# led_demo-v2.net
KiCad netlist of a schematic drawn in EAGLE
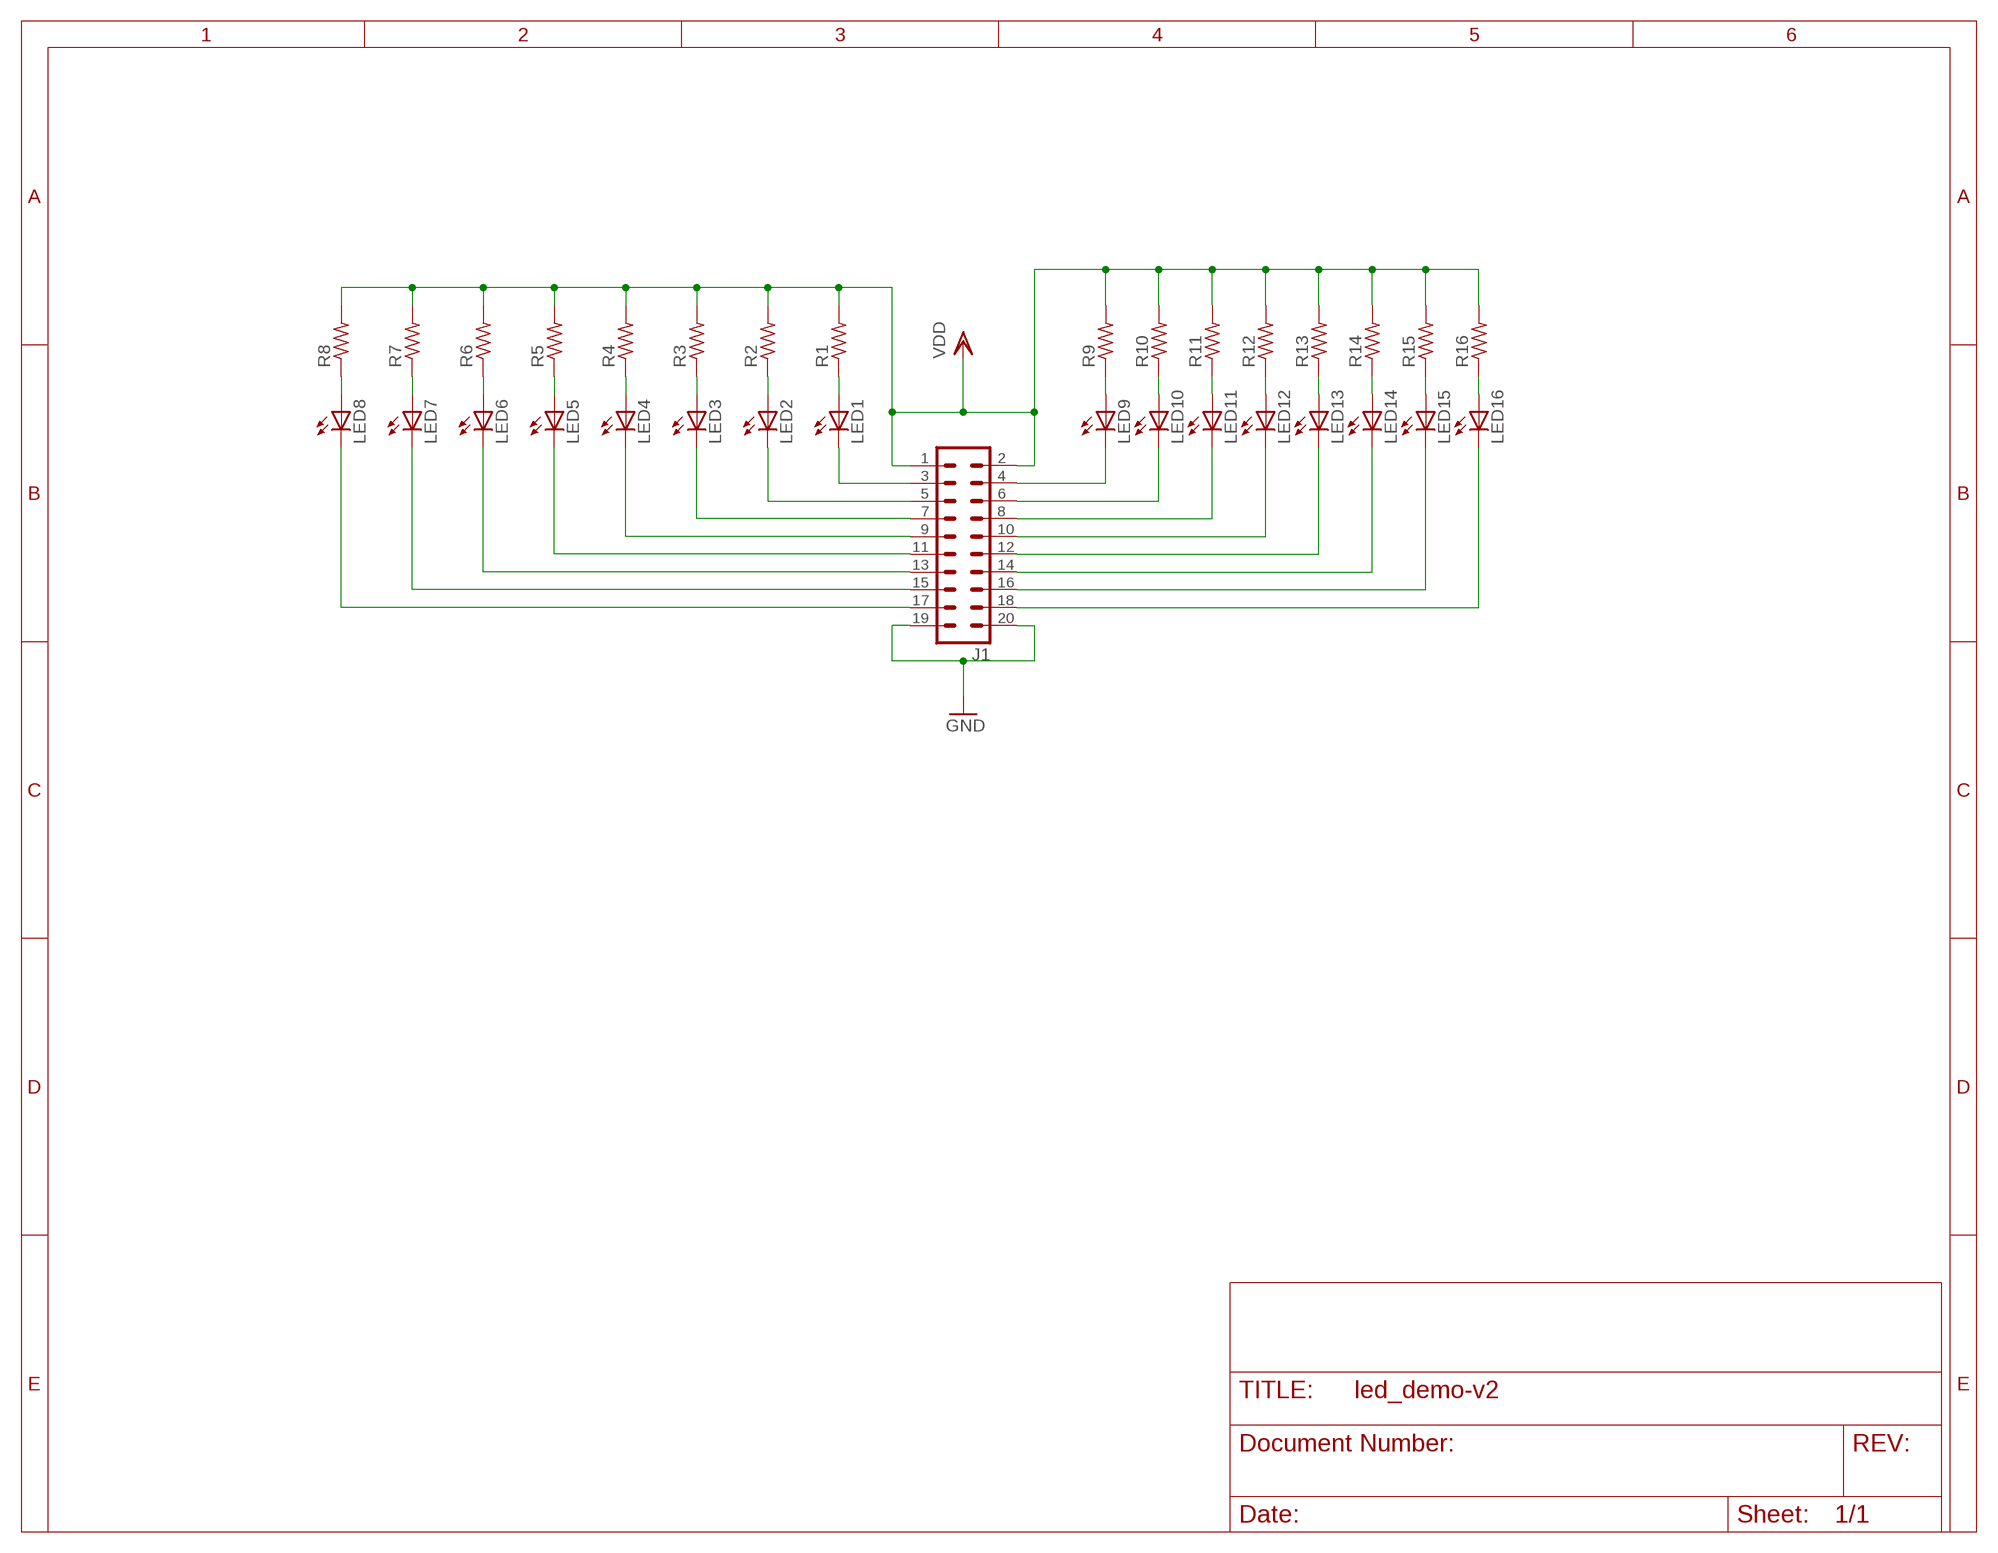
[diagram p0: schematic, sheet 1]

(export (version "E")
  (design (tool "Eeschema 10.0.6"))
  (components
    (comp (ref "J1")
      (value "MA10-2")
      (footprint "eagle-import:MA10-2")
      (libsource (lib "eagle-import") (part "MA10-2"))
    )
    (comp (ref "LED1")
      (value "LED3MM")
      (footprint "eagle-import:LED3MM")
      (libsource (lib "eagle-import") (part "LED3MM"))
    )
    (comp (ref "LED2")
      (value "LED3MM")
      (footprint "eagle-import:LED3MM")
      (libsource (lib "eagle-import") (part "LED3MM"))
    )
    (comp (ref "LED3")
      (value "LED3MM")
      (footprint "eagle-import:LED3MM")
      (libsource (lib "eagle-import") (part "LED3MM"))
    )
    (comp (ref "LED4")
      (value "LED3MM")
      (footprint "eagle-import:LED3MM")
      (libsource (lib "eagle-import") (part "LED3MM"))
    )
    (comp (ref "LED5")
      (value "LED3MM")
      (footprint "eagle-import:LED3MM")
      (libsource (lib "eagle-import") (part "LED3MM"))
    )
    (comp (ref "LED6")
      (value "LED3MM")
      (footprint "eagle-import:LED3MM")
      (libsource (lib "eagle-import") (part "LED3MM"))
    )
    (comp (ref "LED7")
      (value "LED3MM")
      (footprint "eagle-import:LED3MM")
      (libsource (lib "eagle-import") (part "LED3MM"))
    )
    (comp (ref "LED8")
      (value "LED3MM")
      (footprint "eagle-import:LED3MM")
      (libsource (lib "eagle-import") (part "LED3MM"))
    )
    (comp (ref "LED9")
      (value "LED3MM")
      (footprint "eagle-import:LED3MM")
      (libsource (lib "eagle-import") (part "LED3MM"))
    )
    (comp (ref "LED10")
      (value "LED3MM")
      (footprint "eagle-import:LED3MM")
      (libsource (lib "eagle-import") (part "LED3MM"))
    )
    (comp (ref "LED11")
      (value "LED3MM")
      (footprint "eagle-import:LED3MM")
      (libsource (lib "eagle-import") (part "LED3MM"))
    )
    (comp (ref "LED12")
      (value "LED3MM")
      (footprint "eagle-import:LED3MM")
      (libsource (lib "eagle-import") (part "LED3MM"))
    )
    (comp (ref "LED13")
      (value "LED3MM")
      (footprint "eagle-import:LED3MM")
      (libsource (lib "eagle-import") (part "LED3MM"))
    )
    (comp (ref "LED14")
      (value "LED3MM")
      (footprint "eagle-import:LED3MM")
      (libsource (lib "eagle-import") (part "LED3MM"))
    )
    (comp (ref "LED15")
      (value "LED3MM")
      (footprint "eagle-import:LED3MM")
      (libsource (lib "eagle-import") (part "LED3MM"))
    )
    (comp (ref "LED16")
      (value "LED3MM")
      (footprint "eagle-import:LED3MM")
      (libsource (lib "eagle-import") (part "LED3MM"))
    )
    (comp (ref "R1")
      (value "R-US_0204/2V")
      (footprint "eagle-import:0204V")
      (libsource (lib "eagle-import") (part "R-US_0204/2V"))
    )
    (comp (ref "R2")
      (value "R-US_0204/2V")
      (footprint "eagle-import:0204V")
      (libsource (lib "eagle-import") (part "R-US_0204/2V"))
    )
    (comp (ref "R3")
      (value "R-US_0204/2V")
      (footprint "eagle-import:0204V")
      (libsource (lib "eagle-import") (part "R-US_0204/2V"))
    )
    (comp (ref "R4")
      (value "R-US_0204/2V")
      (footprint "eagle-import:0204V")
      (libsource (lib "eagle-import") (part "R-US_0204/2V"))
    )
    (comp (ref "R5")
      (value "R-US_0204/2V")
      (footprint "eagle-import:0204V")
      (libsource (lib "eagle-import") (part "R-US_0204/2V"))
    )
    (comp (ref "R6")
      (value "R-US_0204/2V")
      (footprint "eagle-import:0204V")
      (libsource (lib "eagle-import") (part "R-US_0204/2V"))
    )
    (comp (ref "R7")
      (value "R-US_0204/2V")
      (footprint "eagle-import:0204V")
      (libsource (lib "eagle-import") (part "R-US_0204/2V"))
    )
    (comp (ref "R8")
      (value "R-US_0204/2V")
      (footprint "eagle-import:0204V")
      (libsource (lib "eagle-import") (part "R-US_0204/2V"))
    )
    (comp (ref "R9")
      (value "R-US_0204/2V")
      (footprint "eagle-import:0204V")
      (libsource (lib "eagle-import") (part "R-US_0204/2V"))
    )
    (comp (ref "R10")
      (value "R-US_0204/2V")
      (footprint "eagle-import:0204V")
      (libsource (lib "eagle-import") (part "R-US_0204/2V"))
    )
    (comp (ref "R11")
      (value "R-US_0204/2V")
      (footprint "eagle-import:0204V")
      (libsource (lib "eagle-import") (part "R-US_0204/2V"))
    )
    (comp (ref "R12")
      (value "R-US_0204/2V")
      (footprint "eagle-import:0204V")
      (libsource (lib "eagle-import") (part "R-US_0204/2V"))
    )
    (comp (ref "R13")
      (value "R-US_0204/2V")
      (footprint "eagle-import:0204V")
      (libsource (lib "eagle-import") (part "R-US_0204/2V"))
    )
    (comp (ref "R14")
      (value "R-US_0204/2V")
      (footprint "eagle-import:0204V")
      (libsource (lib "eagle-import") (part "R-US_0204/2V"))
    )
    (comp (ref "R15")
      (value "R-US_0204/2V")
      (footprint "eagle-import:0204V")
      (libsource (lib "eagle-import") (part "R-US_0204/2V"))
    )
    (comp (ref "R16")
      (value "R-US_0204/2V")
      (footprint "eagle-import:0204V")
      (libsource (lib "eagle-import") (part "R-US_0204/2V"))
    )
  )
  (nets
    (net (code "1") (name "GND") (class "Default")
      (node (ref "J1") (pin "19") (pinfunction "19_19") (pintype "passive"))
      (node (ref "J1") (pin "20") (pinfunction "20_20") (pintype "passive"))
    )
    (net (code "2") (name "Net-(LED1-C)") (class "Default")
      (node (ref "J1") (pin "3") (pinfunction "3_3") (pintype "passive"))
      (node (ref "LED1") (pin "K") (pinfunction "C_K") (pintype "passive"))
    )
    (net (code "3") (name "Net-(LED1-PadA)") (class "Default")
      (node (ref "LED1") (pin "A") (pinfunction "A_A") (pintype "passive"))
      (node (ref "R1") (pin "1") (pinfunction "1_1") (pintype "passive"))
    )
    (net (code "4") (name "Net-(LED2-C)") (class "Default")
      (node (ref "J1") (pin "5") (pinfunction "5_5") (pintype "passive"))
      (node (ref "LED2") (pin "K") (pinfunction "C_K") (pintype "passive"))
    )
    (net (code "5") (name "Net-(LED2-PadA)") (class "Default")
      (node (ref "LED2") (pin "A") (pinfunction "A_A") (pintype "passive"))
      (node (ref "R2") (pin "1") (pinfunction "1_1") (pintype "passive"))
    )
    (net (code "6") (name "Net-(LED3-C)") (class "Default")
      (node (ref "J1") (pin "7") (pinfunction "7_7") (pintype "passive"))
      (node (ref "LED3") (pin "K") (pinfunction "C_K") (pintype "passive"))
    )
    (net (code "7") (name "Net-(LED3-PadA)") (class "Default")
      (node (ref "LED3") (pin "A") (pinfunction "A_A") (pintype "passive"))
      (node (ref "R3") (pin "1") (pinfunction "1_1") (pintype "passive"))
    )
    (net (code "8") (name "Net-(LED4-C)") (class "Default")
      (node (ref "J1") (pin "9") (pinfunction "9_9") (pintype "passive"))
      (node (ref "LED4") (pin "K") (pinfunction "C_K") (pintype "passive"))
    )
    (net (code "9") (name "Net-(LED4-PadA)") (class "Default")
      (node (ref "LED4") (pin "A") (pinfunction "A_A") (pintype "passive"))
      (node (ref "R4") (pin "1") (pinfunction "1_1") (pintype "passive"))
    )
    (net (code "10") (name "Net-(LED5-C)") (class "Default")
      (node (ref "J1") (pin "11") (pinfunction "11_11") (pintype "passive"))
      (node (ref "LED5") (pin "K") (pinfunction "C_K") (pintype "passive"))
    )
    (net (code "11") (name "Net-(LED5-PadA)") (class "Default")
      (node (ref "LED5") (pin "A") (pinfunction "A_A") (pintype "passive"))
      (node (ref "R5") (pin "1") (pinfunction "1_1") (pintype "passive"))
    )
    (net (code "12") (name "Net-(LED6-C)") (class "Default")
      (node (ref "J1") (pin "13") (pinfunction "13_13") (pintype "passive"))
      (node (ref "LED6") (pin "K") (pinfunction "C_K") (pintype "passive"))
    )
    (net (code "13") (name "Net-(LED6-PadA)") (class "Default")
      (node (ref "LED6") (pin "A") (pinfunction "A_A") (pintype "passive"))
      (node (ref "R6") (pin "1") (pinfunction "1_1") (pintype "passive"))
    )
    (net (code "14") (name "Net-(LED7-C)") (class "Default")
      (node (ref "J1") (pin "15") (pinfunction "15_15") (pintype "passive"))
      (node (ref "LED7") (pin "K") (pinfunction "C_K") (pintype "passive"))
    )
    (net (code "15") (name "Net-(LED7-PadA)") (class "Default")
      (node (ref "LED7") (pin "A") (pinfunction "A_A") (pintype "passive"))
      (node (ref "R7") (pin "1") (pinfunction "1_1") (pintype "passive"))
    )
    (net (code "16") (name "Net-(LED8-C)") (class "Default")
      (node (ref "J1") (pin "17") (pinfunction "17_17") (pintype "passive"))
      (node (ref "LED8") (pin "K") (pinfunction "C_K") (pintype "passive"))
    )
    (net (code "17") (name "Net-(LED8-PadA)") (class "Default")
      (node (ref "LED8") (pin "A") (pinfunction "A_A") (pintype "passive"))
      (node (ref "R8") (pin "1") (pinfunction "1_1") (pintype "passive"))
    )
    (net (code "18") (name "Net-(LED9-C)") (class "Default")
      (node (ref "J1") (pin "4") (pinfunction "4_4") (pintype "passive"))
      (node (ref "LED9") (pin "K") (pinfunction "C_K") (pintype "passive"))
    )
    (net (code "19") (name "Net-(LED9-PadA)") (class "Default")
      (node (ref "LED9") (pin "A") (pinfunction "A_A") (pintype "passive"))
      (node (ref "R9") (pin "1") (pinfunction "1_1") (pintype "passive"))
    )
    (net (code "20") (name "Net-(LED10-C)") (class "Default")
      (node (ref "J1") (pin "6") (pinfunction "6_6") (pintype "passive"))
      (node (ref "LED10") (pin "K") (pinfunction "C_K") (pintype "passive"))
    )
    (net (code "21") (name "Net-(LED10-PadA)") (class "Default")
      (node (ref "LED10") (pin "A") (pinfunction "A_A") (pintype "passive"))
      (node (ref "R10") (pin "1") (pinfunction "1_1") (pintype "passive"))
    )
    (net (code "22") (name "Net-(LED11-C)") (class "Default")
      (node (ref "J1") (pin "8") (pinfunction "8_8") (pintype "passive"))
      (node (ref "LED11") (pin "K") (pinfunction "C_K") (pintype "passive"))
    )
    (net (code "23") (name "Net-(LED11-PadA)") (class "Default")
      (node (ref "LED11") (pin "A") (pinfunction "A_A") (pintype "passive"))
      (node (ref "R11") (pin "1") (pinfunction "1_1") (pintype "passive"))
    )
    (net (code "24") (name "Net-(LED12-C)") (class "Default")
      (node (ref "J1") (pin "10") (pinfunction "10_10") (pintype "passive"))
      (node (ref "LED12") (pin "K") (pinfunction "C_K") (pintype "passive"))
    )
    (net (code "25") (name "Net-(LED12-PadA)") (class "Default")
      (node (ref "LED12") (pin "A") (pinfunction "A_A") (pintype "passive"))
      (node (ref "R12") (pin "1") (pinfunction "1_1") (pintype "passive"))
    )
    (net (code "26") (name "Net-(LED13-C)") (class "Default")
      (node (ref "J1") (pin "12") (pinfunction "12_12") (pintype "passive"))
      (node (ref "LED13") (pin "K") (pinfunction "C_K") (pintype "passive"))
    )
    (net (code "27") (name "Net-(LED13-PadA)") (class "Default")
      (node (ref "LED13") (pin "A") (pinfunction "A_A") (pintype "passive"))
      (node (ref "R13") (pin "1") (pinfunction "1_1") (pintype "passive"))
    )
    (net (code "28") (name "Net-(LED14-C)") (class "Default")
      (node (ref "J1") (pin "14") (pinfunction "14_14") (pintype "passive"))
      (node (ref "LED14") (pin "K") (pinfunction "C_K") (pintype "passive"))
    )
    (net (code "29") (name "Net-(LED14-PadA)") (class "Default")
      (node (ref "LED14") (pin "A") (pinfunction "A_A") (pintype "passive"))
      (node (ref "R14") (pin "1") (pinfunction "1_1") (pintype "passive"))
    )
    (net (code "30") (name "Net-(LED15-C)") (class "Default")
      (node (ref "J1") (pin "16") (pinfunction "16_16") (pintype "passive"))
      (node (ref "LED15") (pin "K") (pinfunction "C_K") (pintype "passive"))
    )
    (net (code "31") (name "Net-(LED15-PadA)") (class "Default")
      (node (ref "LED15") (pin "A") (pinfunction "A_A") (pintype "passive"))
      (node (ref "R15") (pin "1") (pinfunction "1_1") (pintype "passive"))
    )
    (net (code "32") (name "Net-(LED16-C)") (class "Default")
      (node (ref "J1") (pin "18") (pinfunction "18_18") (pintype "passive"))
      (node (ref "LED16") (pin "K") (pinfunction "C_K") (pintype "passive"))
    )
    (net (code "33") (name "Net-(LED16-PadA)") (class "Default")
      (node (ref "LED16") (pin "A") (pinfunction "A_A") (pintype "passive"))
      (node (ref "R16") (pin "1") (pinfunction "1_1") (pintype "passive"))
    )
    (net (code "34") (name "VDD") (class "Default")
      (node (ref "J1") (pin "1") (pinfunction "1_1") (pintype "passive"))
      (node (ref "J1") (pin "2") (pinfunction "2_2") (pintype "passive"))
      (node (ref "R1") (pin "2") (pinfunction "2_2") (pintype "passive"))
      (node (ref "R10") (pin "2") (pinfunction "2_2") (pintype "passive"))
      (node (ref "R11") (pin "2") (pinfunction "2_2") (pintype "passive"))
      (node (ref "R12") (pin "2") (pinfunction "2_2") (pintype "passive"))
      (node (ref "R13") (pin "2") (pinfunction "2_2") (pintype "passive"))
      (node (ref "R14") (pin "2") (pinfunction "2_2") (pintype "passive"))
      (node (ref "R15") (pin "2") (pinfunction "2_2") (pintype "passive"))
      (node (ref "R16") (pin "2") (pinfunction "2_2") (pintype "passive"))
      (node (ref "R2") (pin "2") (pinfunction "2_2") (pintype "passive"))
      (node (ref "R3") (pin "2") (pinfunction "2_2") (pintype "passive"))
      (node (ref "R4") (pin "2") (pinfunction "2_2") (pintype "passive"))
      (node (ref "R5") (pin "2") (pinfunction "2_2") (pintype "passive"))
      (node (ref "R6") (pin "2") (pinfunction "2_2") (pintype "passive"))
      (node (ref "R7") (pin "2") (pinfunction "2_2") (pintype "passive"))
      (node (ref "R8") (pin "2") (pinfunction "2_2") (pintype "passive"))
      (node (ref "R9") (pin "2") (pinfunction "2_2") (pintype "passive"))
    )
  )
)
